# 05I2S.net
KiCad netlist of a schematic drawn in Altium Designer
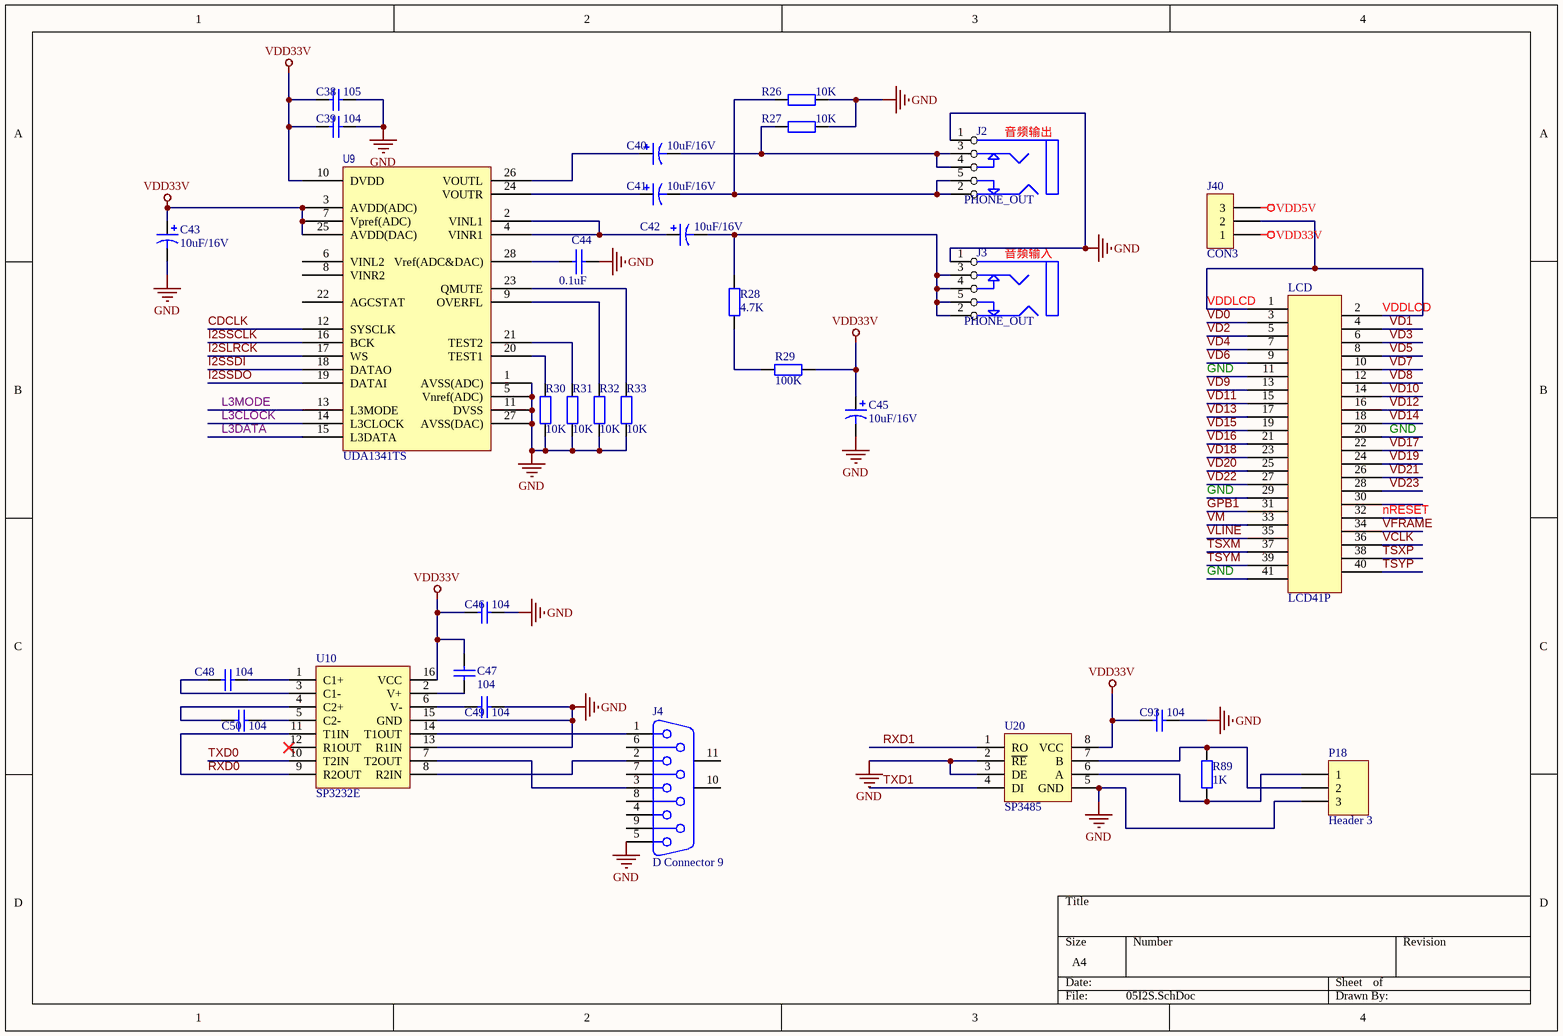
[diagram p0: 05I2S.SchDoc]

(export (version "E")
  (design (tool "Eeschema 10.0.6"))
  (components
    (comp (ref "C38")
      (value "105")
      (footprint "0603A")
      (description "Capacitor")
      (fields (field (name "Comment") "Cap") (field (name "PUBLISHER") "Altium Limited"))
      (libsource (lib "自制Miscellaneous Devices库") (part "Cap"))
    )
    (comp (ref "C39")
      (value "104")
      (footprint "0603A")
      (description "Capacitor")
      (fields (field (name "Comment") "Cap") (field (name "PUBLISHER") "Altium Limited"))
      (libsource (lib "自制Miscellaneous Devices库") (part "Cap"))
    )
    (comp (ref "C40")
      (value "10uF/16V")
      (footprint "1206[3216]")
      (description "Polarized Capacitor (Axial)")
      (fields (field (name "Comment") "Cap Pol2") (field (name "PUBLISHER") "Altium Limited"))
      (libsource (lib "自制Miscellaneous Devices库") (part "Cap Pol2"))
    )
    (comp (ref "C41")
      (value "10uF/16V")
      (footprint "1206[3216]")
      (description "Polarized Capacitor (Axial)")
      (fields (field (name "Comment") "Cap Pol2") (field (name "PUBLISHER") "Altium Limited"))
      (libsource (lib "自制Miscellaneous Devices库") (part "Cap Pol2"))
    )
    (comp (ref "C42")
      (value "10uF/16V")
      (footprint "1206[3216]")
      (description "Polarized Capacitor (Axial)")
      (fields (field (name "Comment") "Cap Pol2") (field (name "PUBLISHER") "Altium Limited"))
      (libsource (lib "自制Miscellaneous Devices库") (part "Cap Pol2"))
    )
    (comp (ref "C43")
      (value "10uF/16V")
      (footprint "1206[3216]")
      (description "Polarized Capacitor (Axial)")
      (fields (field (name "Comment") "Cap Pol2") (field (name "PUBLISHER") "Altium Limited"))
      (libsource (lib "自制Miscellaneous Devices库") (part "Cap Pol2"))
    )
    (comp (ref "C44")
      (value "0.1uF")
      (footprint "0603A")
      (description "Capacitor")
      (libsource (lib "*") (part "CAP"))
    )
    (comp (ref "C45")
      (value "10uF/16V")
      (footprint "1206[3216]")
      (description "Polarized Capacitor (Axial)")
      (fields (field (name "Comment") "Cap Pol2") (field (name "PUBLISHER") "Altium Limited"))
      (libsource (lib "自制Miscellaneous Devices库") (part "Cap Pol2"))
    )
    (comp (ref "C46")
      (value "104")
      (footprint "0603A")
      (description "Capacitor")
      (fields (field (name "Comment") "Cap") (field (name "PUBLISHER") "Altium Limited"))
      (libsource (lib "自制Miscellaneous Devices库") (part "Cap"))
    )
    (comp (ref "C47")
      (value "104")
      (footprint "0603A")
      (description "Capacitor")
      (fields (field (name "Comment") "Cap") (field (name "PUBLISHER") "Altium Limited"))
      (libsource (lib "自制Miscellaneous Devices库") (part "Cap"))
    )
    (comp (ref "C48")
      (value "104")
      (footprint "0603A")
      (description "Capacitor")
      (fields (field (name "Comment") "Cap") (field (name "PUBLISHER") "Altium Limited"))
      (libsource (lib "自制Miscellaneous Devices库") (part "Cap"))
    )
    (comp (ref "C49")
      (value "104")
      (footprint "0603A")
      (description "Capacitor")
      (fields (field (name "Comment") "Cap") (field (name "PUBLISHER") "Altium Limited"))
      (libsource (lib "自制Miscellaneous Devices库") (part "Cap"))
    )
    (comp (ref "C50")
      (value "104")
      (footprint "0603A")
      (description "Capacitor")
      (fields (field (name "Comment") "Cap") (field (name "PUBLISHER") "Altium Limited"))
      (libsource (lib "自制Miscellaneous Devices库") (part "Cap"))
    )
    (comp (ref "C93")
      (value "104")
      (footprint "0603A")
      (description "Capacitor")
      (fields (field (name "Comment") "Cap") (field (name "PUBLISHER") "Altium Limited"))
      (libsource (lib "自制Miscellaneous Devices库") (part "Cap"))
    )
    (comp (ref "J2")
      (value "PHONE_OUT")
      (footprint "ST-3150-5N")
      (libsource (lib "自制原理图元件库") (part "PHONEJACK STEREO SW"))
    )
    (comp (ref "J3")
      (value "PHONE_OUT")
      (footprint "ST-3150-5N")
      (libsource (lib "自制原理图元件库") (part "PHONEJACK STEREO SW"))
    )
    (comp (ref "J4")
      (value "D Connector 9")
      (footprint "DSUB1.385-2H9")
      (description "Receptacle Assembly, 9 Position, Right Angle")
      (fields (field (name "PUBLISHER") "Altium Limited"))
      (libsource (lib "自制Miscellaneous Connectors库") (part "D Connector 9"))
    )
    (comp (ref "J40")
      (value "CON3")
      (footprint "HDR1X3")
      (description "Connector")
      (libsource (lib "*") (part "CON3"))
    )
    (comp (ref "LCD") (value "LCD41P") (footprint "FPC40") (libsource (lib "*") (part "LCD41P")))
    (comp (ref "P18")
      (value "Header 3")
      (footprint "HDR1X3")
      (description "Header, 3-Pin")
      (fields (field (name "PUBLISHER") "Altium Limited"))
      (libsource (lib "自制Miscellaneous Connectors库") (part "Header 3"))
    )
    (comp (ref "R26")
      (value "10K")
      (footprint "0603R")
      (description "Resistor")
      (fields (field (name "Comment") "Res2") (field (name "PUBLISHER") "Altium Limited"))
      (libsource (lib "") (part "Res2_1"))
    )
    (comp (ref "R27")
      (value "10K")
      (footprint "0603R")
      (description "Resistor")
      (fields (field (name "Comment") "Res2") (field (name "PUBLISHER") "Altium Limited"))
      (libsource (lib "") (part "Res2_1"))
    )
    (comp (ref "R28")
      (value "4.7K")
      (footprint "0603R")
      (description "Resistor")
      (fields (field (name "Comment") "Res2") (field (name "PUBLISHER") "Altium Limited"))
      (libsource (lib "自制Miscellaneous Devices库") (part "Res2"))
    )
    (comp (ref "R29")
      (value "100K")
      (footprint "0603R")
      (description "Resistor")
      (fields (field (name "Comment") "Res2") (field (name "PUBLISHER") "Altium Limited"))
      (libsource (lib "") (part "Res2_2"))
    )
    (comp (ref "R30")
      (value "10K")
      (footprint "0603R")
      (description "Resistor")
      (fields (field (name "Comment") "Res2") (field (name "PUBLISHER") "Altium Limited"))
      (libsource (lib "自制Miscellaneous Devices库") (part "Res2"))
    )
    (comp (ref "R31")
      (value "10K")
      (footprint "0603R")
      (description "Resistor")
      (fields (field (name "Comment") "Res2") (field (name "PUBLISHER") "Altium Limited"))
      (libsource (lib "自制Miscellaneous Devices库") (part "Res2"))
    )
    (comp (ref "R32")
      (value "10K")
      (footprint "0603R")
      (description "Resistor")
      (fields (field (name "Comment") "Res2") (field (name "PUBLISHER") "Altium Limited"))
      (libsource (lib "自制Miscellaneous Devices库") (part "Res2"))
    )
    (comp (ref "R33")
      (value "10K")
      (footprint "0603R")
      (description "Resistor")
      (fields (field (name "Comment") "Res2") (field (name "PUBLISHER") "Altium Limited"))
      (libsource (lib "自制Miscellaneous Devices库") (part "Res2"))
    )
    (comp (ref "R89")
      (value "1K")
      (footprint "0603R")
      (description "Resistor")
      (fields (field (name "Comment") "Res2") (field (name "PUBLISHER") "Altium Limited"))
      (libsource (lib "自制Miscellaneous Devices库") (part "Res2"))
    )
    (comp (ref "U9")
      (value "UDA1341TS")
      (footprint "SOP28")
      (libsource (lib "自制原理图元件库") (part "UDA1341TS_1"))
    )
    (comp (ref "U10")
      (value "SP3232E")
      (footprint "SOP16_SP3232")
      (libsource (lib "自制原理图元件库") (part "SP3232E"))
    )
    (comp (ref "U20")
      (value "SP3485")
      (footprint "PCBComponent_1")
      (libsource (lib "自制原理图元件库") (part "SP3485"))
    )
  )
  (nets
    (net (code "1") (name "/CDCLK") (class "Default")
      (node (ref "U9") (pin "12") (pinfunction "SYSCLK_12") (pintype "passive"))
    )
    (net (code "2") (name "/GPB1") (class "Default") (node (ref "LCD") (pin "31") (pintype "passive")))
    (net (code "3") (name "/I2SLRCK") (class "Default")
      (node (ref "U9") (pin "17") (pinfunction "WS_17") (pintype "passive"))
    )
    (net (code "4") (name "/I2SSCLK") (class "Default")
      (node (ref "U9") (pin "16") (pinfunction "BCK_16") (pintype "passive"))
    )
    (net (code "5") (name "/I2SSDI") (class "Default")
      (node (ref "U9") (pin "18") (pinfunction "DATAO_18") (pintype "passive"))
    )
    (net (code "6") (name "/I2SSDO") (class "Default")
      (node (ref "U9") (pin "19") (pinfunction "DATAI_19") (pintype "passive"))
    )
    (net (code "7") (name "/L3CLOCK") (class "Default")
      (node (ref "U9") (pin "14") (pinfunction "L3CLOCK_14") (pintype "passive"))
    )
    (net (code "8") (name "/L3DATA") (class "Default")
      (node (ref "U9") (pin "15") (pinfunction "L3DATA_15") (pintype "passive"))
    )
    (net (code "9") (name "/L3MODE") (class "Default")
      (node (ref "U9") (pin "13") (pinfunction "L3MODE_13") (pintype "passive"))
    )
    (net (code "10") (name "/RXD0") (class "Default")
      (node (ref "U10") (pin "11") (pinfunction "T1IN_11") (pintype "passive"))
      (node (ref "U10") (pin "9") (pinfunction "R2OUT_9") (pintype "passive"))
    )
    (net (code "11") (name "/RXD1") (class "Default")
      (node (ref "U20") (pin "1") (pinfunction "RO_1") (pintype "passive"))
    )
    (net (code "12") (name "/TSXM") (class "Default") (node (ref "LCD") (pin "37") (pintype "passive")))
    (net (code "13") (name "/TSXP") (class "Default") (node (ref "LCD") (pin "38") (pintype "passive")))
    (net (code "14") (name "/TSYM") (class "Default") (node (ref "LCD") (pin "39") (pintype "passive")))
    (net (code "15") (name "/TSYP") (class "Default") (node (ref "LCD") (pin "40") (pintype "passive")))
    (net (code "16") (name "/TXD0") (class "Default")
      (node (ref "U10") (pin "10") (pinfunction "T2IN_10") (pintype "passive"))
    )
    (net (code "17") (name "/TXD1") (class "Default")
      (node (ref "U20") (pin "4") (pinfunction "DI_4") (pintype "passive"))
    )
    (net (code "18") (name "/VCLK") (class "Default") (node (ref "LCD") (pin "36") (pintype "passive")))
    (net (code "19") (name "/VD0") (class "Default") (node (ref "LCD") (pin "3") (pintype "passive")))
    (net (code "20") (name "/VD1") (class "Default") (node (ref "LCD") (pin "4") (pintype "passive")))
    (net (code "21") (name "/VD2") (class "Default") (node (ref "LCD") (pin "5") (pintype "passive")))
    (net (code "22") (name "/VD3") (class "Default") (node (ref "LCD") (pin "6") (pintype "passive")))
    (net (code "23") (name "/VD4") (class "Default") (node (ref "LCD") (pin "7") (pintype "passive")))
    (net (code "24") (name "/VD5") (class "Default") (node (ref "LCD") (pin "8") (pintype "passive")))
    (net (code "25") (name "/VD6") (class "Default") (node (ref "LCD") (pin "9") (pintype "passive")))
    (net (code "26") (name "/VD7") (class "Default") (node (ref "LCD") (pin "10") (pintype "passive")))
    (net (code "27") (name "/VD8") (class "Default") (node (ref "LCD") (pin "12") (pintype "passive")))
    (net (code "28") (name "/VD9") (class "Default") (node (ref "LCD") (pin "13") (pintype "passive")))
    (net (code "29") (name "/VD10") (class "Default") (node (ref "LCD") (pin "14") (pintype "passive")))
    (net (code "30") (name "/VD11") (class "Default") (node (ref "LCD") (pin "15") (pintype "passive")))
    (net (code "31") (name "/VD12") (class "Default") (node (ref "LCD") (pin "16") (pintype "passive")))
    (net (code "32") (name "/VD13") (class "Default") (node (ref "LCD") (pin "17") (pintype "passive")))
    (net (code "33") (name "/VD14") (class "Default") (node (ref "LCD") (pin "18") (pintype "passive")))
    (net (code "34") (name "/VD15") (class "Default") (node (ref "LCD") (pin "19") (pintype "passive")))
    (net (code "35") (name "/VD16") (class "Default") (node (ref "LCD") (pin "21") (pintype "passive")))
    (net (code "36") (name "/VD17") (class "Default") (node (ref "LCD") (pin "22") (pintype "passive")))
    (net (code "37") (name "/VD18") (class "Default") (node (ref "LCD") (pin "23") (pintype "passive")))
    (net (code "38") (name "/VD19") (class "Default") (node (ref "LCD") (pin "24") (pintype "passive")))
    (net (code "39") (name "/VD20") (class "Default") (node (ref "LCD") (pin "25") (pintype "passive")))
    (net (code "40") (name "/VD21") (class "Default") (node (ref "LCD") (pin "26") (pintype "passive")))
    (net (code "41") (name "/VD22") (class "Default") (node (ref "LCD") (pin "27") (pintype "passive")))
    (net (code "42") (name "/VD23") (class "Default") (node (ref "LCD") (pin "28") (pintype "passive")))
    (net (code "43") (name "/VDDLCD") (class "Default")
      (node (ref "J40") (pin "2") (pinfunction "2_2") (pintype "passive"))
      (node (ref "LCD") (pin "1") (pintype "passive"))
      (node (ref "LCD") (pin "2") (pintype "passive"))
    )
    (net (code "44") (name "/VFRAME") (class "Default") (node (ref "LCD") (pin "34") (pintype "passive")))
    (net (code "45") (name "/VLINE") (class "Default") (node (ref "LCD") (pin "35") (pintype "passive")))
    (net (code "46") (name "/VM") (class "Default") (node (ref "LCD") (pin "33") (pintype "passive")))
    (net (code "47") (name "/nRESET") (class "Default") (node (ref "LCD") (pin "32") (pintype "passive")))
    (net (code "48") (name "GND") (class "Default")
      (node (ref "C38") (pin "1") (pinfunction "1_1") (pintype "passive"))
      (node (ref "C39") (pin "1") (pinfunction "1_1") (pintype "passive"))
      (node (ref "C43") (pin "2") (pinfunction "2_2") (pintype "passive"))
      (node (ref "C44") (pin "2") (pinfunction "2_2") (pintype "passive"))
      (node (ref "C45") (pin "2") (pinfunction "2_2") (pintype "passive"))
      (node (ref "C46") (pin "2") (pinfunction "2_2") (pintype "passive"))
      (node (ref "C49") (pin "2") (pinfunction "2_2") (pintype "passive"))
      (node (ref "C93") (pin "2") (pinfunction "2_2") (pintype "passive"))
      (node (ref "J2") (pin "1") (pinfunction "A_1") (pintype "passive"))
      (node (ref "J3") (pin "1") (pinfunction "A_1") (pintype "passive"))
      (node (ref "J4") (pin "5") (pinfunction "5_5") (pintype "passive"))
      (node (ref "LCD") (pin "11") (pintype "passive"))
      (node (ref "LCD") (pin "20") (pintype "passive"))
      (node (ref "LCD") (pin "29") (pintype "passive"))
      (node (ref "LCD") (pin "41") (pintype "passive"))
      (node (ref "P18") (pin "3") (pinfunction "3_3") (pintype "passive"))
      (node (ref "R26") (pin "2") (pinfunction "2_2") (pintype "passive"))
      (node (ref "R27") (pin "2") (pinfunction "2_2") (pintype "passive"))
      (node (ref "R30") (pin "1") (pinfunction "1_1") (pintype "passive"))
      (node (ref "R31") (pin "1") (pinfunction "1_1") (pintype "passive"))
      (node (ref "R32") (pin "1") (pinfunction "1_1") (pintype "passive"))
      (node (ref "R33") (pin "1") (pinfunction "1_1") (pintype "passive"))
      (node (ref "U10") (pin "13") (pinfunction "R1IN_13") (pintype "passive"))
      (node (ref "U10") (pin "15") (pinfunction "GND_15") (pintype "passive"))
      (node (ref "U20") (pin "2") (pinfunction "~{RE}_2") (pintype "passive"))
      (node (ref "U20") (pin "3") (pinfunction "DE_3") (pintype "passive"))
      (node (ref "U20") (pin "5") (pinfunction "GND_5") (pintype "passive"))
      (node (ref "U9") (pin "1") (pinfunction "AVSS(ADC)_1") (pintype "passive"))
      (node (ref "U9") (pin "11") (pinfunction "DVSS_11") (pintype "passive"))
      (node (ref "U9") (pin "27") (pinfunction "AVSS(DAC)_27") (pintype "passive"))
      (node (ref "U9") (pin "5") (pinfunction "Vnref(ADC)_5") (pintype "passive"))
    )
    (net (code "49") (name "Net-(J2-B)") (class "Default")
      (node (ref "C41") (pin "2") (pinfunction "2_2") (pintype "passive"))
      (node (ref "J2") (pin "2") (pinfunction "B_2") (pintype "passive"))
      (node (ref "J2") (pin "5") (pinfunction "F_5") (pintype "passive"))
      (node (ref "R26") (pin "1") (pinfunction "1_1") (pintype "passive"))
    )
    (net (code "50") (name "Net-(J2-C)") (class "Default")
      (node (ref "C40") (pin "2") (pinfunction "2_2") (pintype "passive"))
      (node (ref "J2") (pin "3") (pinfunction "C_3") (pintype "passive"))
      (node (ref "J2") (pin "4") (pinfunction "E_4") (pintype "passive"))
      (node (ref "R27") (pin "1") (pinfunction "1_1") (pintype "passive"))
    )
    (net (code "51") (name "Net-(J3-B)") (class "Default")
      (node (ref "C42") (pin "2") (pinfunction "2_2") (pintype "passive"))
      (node (ref "J3") (pin "2") (pinfunction "B_2") (pintype "passive"))
      (node (ref "J3") (pin "3") (pinfunction "C_3") (pintype "passive"))
      (node (ref "J3") (pin "4") (pinfunction "E_4") (pintype "passive"))
      (node (ref "J3") (pin "5") (pinfunction "F_5") (pintype "passive"))
      (node (ref "R28") (pin "2") (pinfunction "2_2") (pintype "passive"))
    )
    (net (code "52") (name "Net-(R28-Pad1)") (class "Default")
      (node (ref "R28") (pin "1") (pinfunction "1_1") (pintype "passive"))
      (node (ref "R29") (pin "2") (pinfunction "2_2") (pintype "passive"))
    )
    (net (code "53") (name "Net-(U9-OVERFL)") (class "Default")
      (node (ref "R32") (pin "2") (pinfunction "2_2") (pintype "passive"))
      (node (ref "U9") (pin "9") (pinfunction "OVERFL_9") (pintype "passive"))
    )
    (net (code "54") (name "Net-(U9-QMUTE)") (class "Default")
      (node (ref "R33") (pin "2") (pinfunction "2_2") (pintype "passive"))
      (node (ref "U9") (pin "23") (pinfunction "QMUTE_23") (pintype "passive"))
    )
    (net (code "55") (name "Net-(U9-TEST1)") (class "Default")
      (node (ref "R30") (pin "2") (pinfunction "2_2") (pintype "passive"))
      (node (ref "U9") (pin "20") (pinfunction "TEST1_20") (pintype "passive"))
    )
    (net (code "56") (name "Net-(U9-TEST2)") (class "Default")
      (node (ref "R31") (pin "2") (pinfunction "2_2") (pintype "passive"))
      (node (ref "U9") (pin "21") (pinfunction "TEST2_21") (pintype "passive"))
    )
    (net (code "57") (name "Net-(U9-VINL1)") (class "Default")
      (node (ref "C42") (pin "1") (pinfunction "1_1") (pintype "passive"))
      (node (ref "U9") (pin "2") (pinfunction "VINL1_2") (pintype "passive"))
      (node (ref "U9") (pin "4") (pinfunction "VINR1_4") (pintype "passive"))
    )
    (net (code "58") (name "Net-(U9-VOUTL)") (class "Default")
      (node (ref "C40") (pin "1") (pinfunction "1_1") (pintype "passive"))
      (node (ref "U9") (pin "26") (pinfunction "VOUTL_26") (pintype "passive"))
    )
    (net (code "59") (name "Net-(U9-VOUTR)") (class "Default")
      (node (ref "C41") (pin "1") (pinfunction "1_1") (pintype "passive"))
      (node (ref "U9") (pin "24") (pinfunction "VOUTR_24") (pintype "passive"))
    )
    (net (code "60") (name "Net-(U9-Vref(ADC&DAC))") (class "Default")
      (node (ref "C44") (pin "1") (pinfunction "1_1") (pintype "passive"))
      (node (ref "U9") (pin "28") (pinfunction "Vref(ADC&DAC)_28") (pintype "passive"))
    )
    (net (code "61") (name "Net-(U10-C1+)") (class "Default")
      (node (ref "C48") (pin "2") (pinfunction "2_2") (pintype "passive"))
      (node (ref "U10") (pin "1") (pinfunction "C1+_1") (pintype "passive"))
    )
    (net (code "62") (name "Net-(U10-C1-)") (class "Default")
      (node (ref "C48") (pin "1") (pinfunction "1_1") (pintype "passive"))
      (node (ref "U10") (pin "3") (pinfunction "C1-_3") (pintype "passive"))
    )
    (net (code "63") (name "Net-(U10-C2+)") (class "Default")
      (node (ref "C50") (pin "1") (pinfunction "1_1") (pintype "passive"))
      (node (ref "U10") (pin "4") (pinfunction "C2+_4") (pintype "passive"))
    )
    (net (code "64") (name "Net-(U10-C2-)") (class "Default")
      (node (ref "C50") (pin "2") (pinfunction "2_2") (pintype "passive"))
      (node (ref "U10") (pin "5") (pinfunction "C2-_5") (pintype "passive"))
    )
    (net (code "65") (name "Net-(U10-R2IN)") (class "Default")
      (node (ref "J4") (pin "2") (pinfunction "2_2") (pintype "passive"))
      (node (ref "U10") (pin "8") (pinfunction "R2IN_8") (pintype "passive"))
    )
    (net (code "66") (name "Net-(U10-T1OUT)") (class "Default")
      (node (ref "J4") (pin "1") (pinfunction "1_1") (pintype "passive"))
      (node (ref "U10") (pin "14") (pinfunction "T1OUT_14") (pintype "passive"))
    )
    (net (code "67") (name "Net-(U10-T2OUT)") (class "Default")
      (node (ref "J4") (pin "3") (pinfunction "3_3") (pintype "passive"))
      (node (ref "U10") (pin "7") (pinfunction "T2OUT_7") (pintype "passive"))
    )
    (net (code "68") (name "Net-(U10-V+)") (class "Default")
      (node (ref "C47") (pin "1") (pinfunction "1_1") (pintype "passive"))
      (node (ref "U10") (pin "2") (pinfunction "V+_2") (pintype "passive"))
    )
    (net (code "69") (name "Net-(U10-V-)") (class "Default")
      (node (ref "C49") (pin "1") (pinfunction "1_1") (pintype "passive"))
      (node (ref "U10") (pin "6") (pinfunction "V-_6") (pintype "passive"))
    )
    (net (code "70") (name "Net-(U20-A)") (class "Default")
      (node (ref "P18") (pin "1") (pinfunction "1_1") (pintype "passive"))
      (node (ref "R89") (pin "1") (pinfunction "1_1") (pintype "passive"))
      (node (ref "U20") (pin "6") (pinfunction "A_6") (pintype "passive"))
    )
    (net (code "71") (name "Net-(U20-B)") (class "Default")
      (node (ref "P18") (pin "2") (pinfunction "2_2") (pintype "passive"))
      (node (ref "R89") (pin "2") (pinfunction "2_2") (pintype "passive"))
      (node (ref "U20") (pin "7") (pinfunction "B_7") (pintype "passive"))
    )
    (net (code "72") (name "VDD5V") (class "Default")
      (node (ref "J40") (pin "3") (pinfunction "3_3") (pintype "passive"))
    )
    (net (code "73") (name "VDD33V") (class "Default")
      (node (ref "C38") (pin "2") (pinfunction "2_2") (pintype "passive"))
      (node (ref "C39") (pin "2") (pinfunction "2_2") (pintype "passive"))
      (node (ref "C43") (pin "1") (pinfunction "1_1") (pintype "passive"))
      (node (ref "C45") (pin "1") (pinfunction "1_1") (pintype "passive"))
      (node (ref "C46") (pin "1") (pinfunction "1_1") (pintype "passive"))
      (node (ref "C47") (pin "2") (pinfunction "2_2") (pintype "passive"))
      (node (ref "C93") (pin "1") (pinfunction "1_1") (pintype "passive"))
      (node (ref "J40") (pin "1") (pinfunction "1_1") (pintype "passive"))
      (node (ref "R29") (pin "1") (pinfunction "1_1") (pintype "passive"))
      (node (ref "U10") (pin "16") (pinfunction "VCC_16") (pintype "passive"))
      (node (ref "U20") (pin "8") (pinfunction "VCC_8") (pintype "passive"))
      (node (ref "U9") (pin "10") (pinfunction "DVDD_10") (pintype "passive"))
      (node (ref "U9") (pin "25") (pinfunction "AVDD(DAC)_25") (pintype "passive"))
      (node (ref "U9") (pin "3") (pinfunction "AVDD(ADC)_3") (pintype "passive"))
      (node (ref "U9") (pin "7") (pinfunction "Vpref(ADC)_7") (pintype "passive"))
    )
    (net (code "74") (name "unconnected-(J4-MH1-Pad10)") (class "Default")
      (node (ref "J4") (pin "10") (pinfunction "MH1_10") (pintype "passive"))
    )
    (net (code "75") (name "unconnected-(J4-MH2-Pad11)") (class "Default")
      (node (ref "J4") (pin "11") (pinfunction "MH2_11") (pintype "passive"))
    )
    (net (code "76") (name "unconnected-(J4-Pad4)") (class "Default")
      (node (ref "J4") (pin "4") (pinfunction "4_4") (pintype "passive"))
    )
    (net (code "77") (name "unconnected-(J4-Pad6)") (class "Default")
      (node (ref "J4") (pin "6") (pinfunction "6_6") (pintype "passive"))
    )
    (net (code "78") (name "unconnected-(J4-Pad7)") (class "Default")
      (node (ref "J4") (pin "7") (pinfunction "7_7") (pintype "passive"))
    )
    (net (code "79") (name "unconnected-(J4-Pad8)") (class "Default")
      (node (ref "J4") (pin "8") (pinfunction "8_8") (pintype "passive"))
    )
    (net (code "80") (name "unconnected-(J4-Pad9)") (class "Default")
      (node (ref "J4") (pin "9") (pinfunction "9_9") (pintype "passive"))
    )
    (net (code "81") (name "unconnected-(LCD-Pad30)") (class "Default")
      (node (ref "LCD") (pin "30") (pintype "passive"))
    )
    (net (code "82") (name "unconnected-(U9-AGCSTAT-Pad22)") (class "Default")
      (node (ref "U9") (pin "22") (pinfunction "AGCSTAT_22") (pintype "passive"))
    )
    (net (code "83") (name "unconnected-(U9-VINL2-Pad6)") (class "Default")
      (node (ref "U9") (pin "6") (pinfunction "VINL2_6") (pintype "passive"))
    )
    (net (code "84") (name "unconnected-(U9-VINR2-Pad8)") (class "Default")
      (node (ref "U9") (pin "8") (pinfunction "VINR2_8") (pintype "passive"))
    )
    (net (code "85") (name "unconnected-(U10-R1OUT-Pad12)") (class "Default")
      (node (ref "U10") (pin "12") (pinfunction "R1OUT_12") (pintype "passive+no_connect"))
    )
  )
)
